# Processamento.net
KiCad netlist of a schematic drawn in Altium Designer
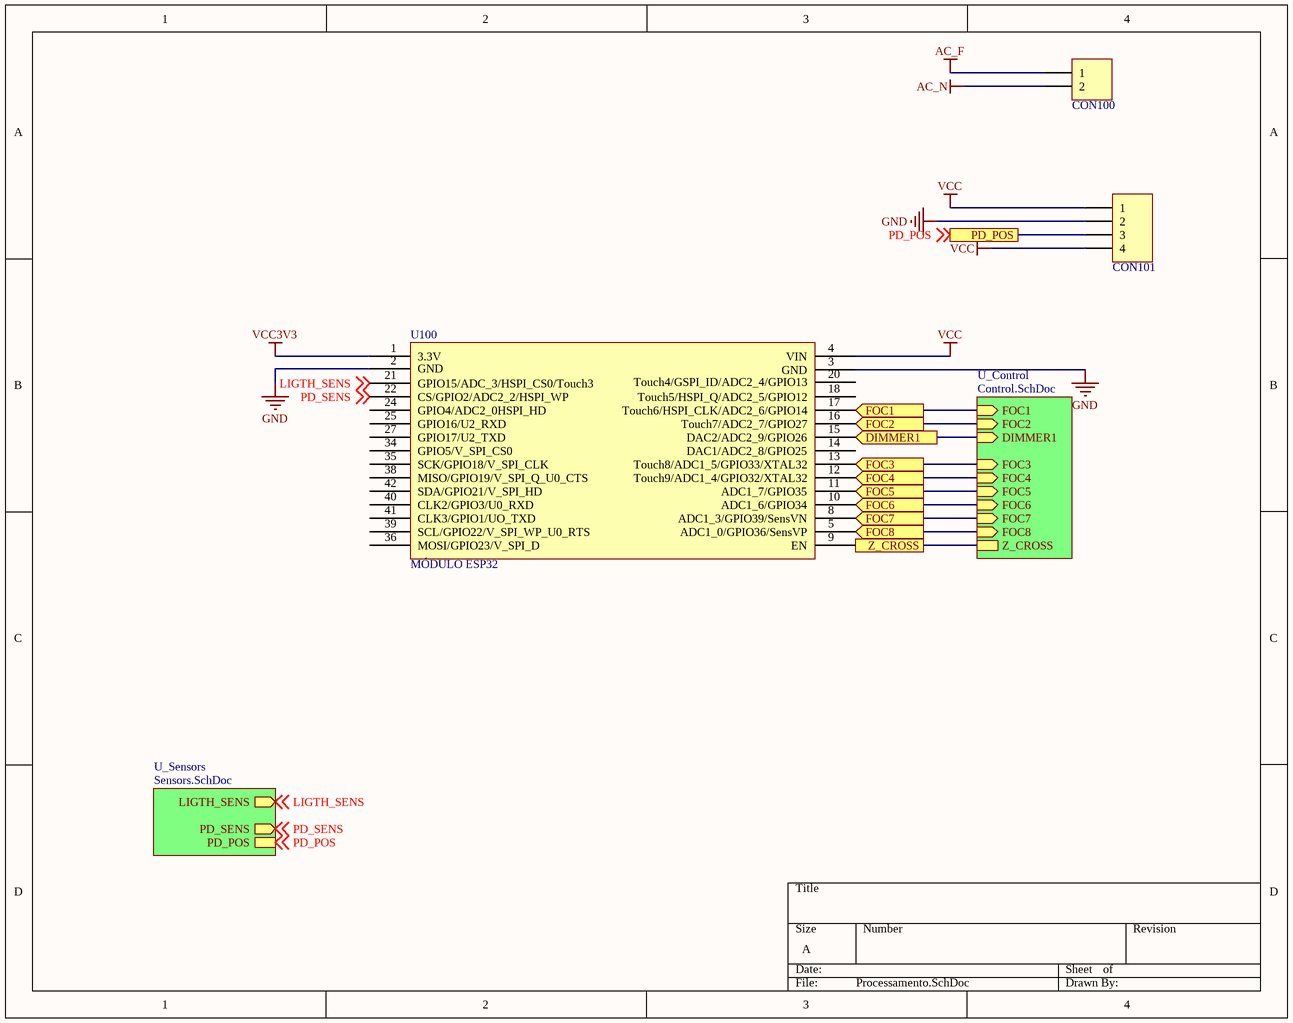
[diagram p0: Processamento.SchDoc]

(export (version "E")
  (design (tool "Eeschema 10.0.6"))
  (components
    (comp (ref "CON100")
      (value "TERM BLOCK 2POS")
      (footprint "STL:MSTBA 2G")
      (description "TERM BLOCK HDR 2POS R/A 5.08MM")
      (fields
        (field (name "MANUFACTURER") "Phoenix Contact")
        (field (name "MANUFACTURER PART NUMBER") "1757242")
      )
      (libsource (lib "STL") (part "TERM BLOCK HEADER 2POS R/A 5.08MM"))
    )
    (comp (ref "CON101")
      (value "TERM BLOCK 4POS")
      (footprint "STL:MSTBA 4G")
      (description "TERM BLOCK HDR 4POS R/A 5.08MM")
      (libsource (lib "STL") (part "TERM BLOCK HEADER 4POS R/A 5.08MM"))
    )
    (comp (ref "U100")
      (value "MÓDULO ESP32")
      (footprint "STL:ESP32 MOD")
      (libsource (lib "STL") (part "IC MICOCONTROLADOR ESP32 MODULO"))
    )
  )
  (nets
    (net (code "1") (name "/DIMMER1") (class "Default")
      (node (ref "U100") (pin "15") (pinfunction "DAC2/ADC2_9/GPIO26_15") (pintype "passive"))
    )
    (net (code "2") (name "/FOC1") (class "Default")
      (node (ref "U100") (pin "17") (pinfunction "Touch6/HSPI_CLK/ADC2_6/GPIO14_17") (pintype "passive"))
    )
    (net (code "3") (name "/FOC2") (class "Default")
      (node (ref "U100") (pin "16") (pinfunction "Touch7/ADC2_7/GPIO27_16") (pintype "passive"))
    )
    (net (code "4") (name "/FOC3") (class "Default")
      (node (ref "U100") (pin "13") (pinfunction "Touch8/ADC1_5/GPIO33/XTAL32_13") (pintype "passive"))
    )
    (net (code "5") (name "/FOC4") (class "Default")
      (node (ref "U100") (pin "12") (pinfunction "Touch9/ADC1_4/GPIO32/XTAL32_12") (pintype "passive"))
    )
    (net (code "6") (name "/FOC5") (class "Default")
      (node (ref "U100") (pin "11") (pinfunction "ADC1_7/GPIO35_11") (pintype "passive"))
    )
    (net (code "7") (name "/FOC6") (class "Default")
      (node (ref "U100") (pin "10") (pinfunction "ADC1_6/GPIO34_10") (pintype "passive"))
    )
    (net (code "8") (name "/FOC7") (class "Default")
      (node (ref "U100") (pin "8") (pinfunction "ADC1_3/GPIO39/SensVN_8") (pintype "passive"))
    )
    (net (code "9") (name "/FOC8") (class "Default")
      (node (ref "U100") (pin "5") (pinfunction "ADC1_0/GPIO36/SensVP_5") (pintype "passive"))
    )
    (net (code "10") (name "/Z_CROSS") (class "Default")
      (node (ref "U100") (pin "9") (pinfunction "EN_9") (pintype "passive"))
    )
    (net (code "11") (name "AC_F") (class "Default")
      (node (ref "CON100") (pin "1") (pinfunction "1_1") (pintype "passive"))
    )
    (net (code "12") (name "AC_N") (class "Default")
      (node (ref "CON100") (pin "2") (pinfunction "2_2") (pintype "passive"))
    )
    (net (code "13") (name "GND") (class "Default")
      (node (ref "CON101") (pin "2") (pinfunction "2_2") (pintype "passive"))
      (node (ref "U100") (pin "2") (pinfunction "GND_2") (pintype "power_in"))
      (node (ref "U100") (pin "3") (pinfunction "GND_3") (pintype "passive"))
    )
    (net (code "14") (name "LIGTH_SENS") (class "Default")
      (node (ref "U100") (pin "21") (pinfunction "GPIO15/ADC_3/HSPI_CS0/Touch3_21") (pintype "passive"))
    )
    (net (code "15") (name "PD_POS") (class "Default")
      (node (ref "CON101") (pin "3") (pinfunction "3_3") (pintype "passive"))
    )
    (net (code "16") (name "PD_SENS") (class "Default")
      (node (ref "U100") (pin "22") (pinfunction "CS/GPIO2/ADC2_2/HSPI_WP_22") (pintype "passive"))
    )
    (net (code "17") (name "VCC") (class "Default")
      (node (ref "CON101") (pin "1") (pinfunction "1_1") (pintype "passive"))
      (node (ref "CON101") (pin "4") (pinfunction "4_4") (pintype "passive"))
      (node (ref "U100") (pin "4") (pinfunction "VIN_4") (pintype "passive"))
    )
    (net (code "18") (name "VCC3V3") (class "Default")
      (node (ref "U100") (pin "1") (pinfunction "3.3V_1") (pintype "power_in"))
    )
    (net (code "19") (name "unconnected-(U100-CLK2{slash}GPIO3{slash}U0_RXD-Pad40)") (class "Default")
      (node (ref "U100") (pin "40") (pinfunction "CLK2/GPIO3/U0_RXD_40") (pintype "passive"))
    )
    (net (code "20") (name "unconnected-(U100-CLK3{slash}GPIO1{slash}UO_TXD-Pad41)") (class "Default")
      (node (ref "U100") (pin "41") (pinfunction "CLK3/GPIO1/UO_TXD_41") (pintype "passive"))
    )
    (net (code "21") (name "unconnected-(U100-DAC1{slash}ADC2_8{slash}GPIO25-Pad14)") (class "Default")
      (node (ref "U100") (pin "14") (pinfunction "DAC1/ADC2_8/GPIO25_14") (pintype "passive"))
    )
    (net (code "22") (name "unconnected-(U100-GPIO4{slash}ADC2_0HSPI_HD-Pad24)") (class "Default")
      (node (ref "U100") (pin "24") (pinfunction "GPIO4/ADC2_0HSPI_HD_24") (pintype "passive"))
    )
    (net (code "23") (name "unconnected-(U100-GPIO5{slash}V_SPI_CS0-Pad34)") (class "Default")
      (node (ref "U100") (pin "34") (pinfunction "GPIO5/V_SPI_CS0_34") (pintype "passive"))
    )
    (net (code "24") (name "unconnected-(U100-GPIO16{slash}U2_RXD-Pad25)") (class "Default")
      (node (ref "U100") (pin "25") (pinfunction "GPIO16/U2_RXD_25") (pintype "passive"))
    )
    (net (code "25") (name "unconnected-(U100-GPIO17{slash}U2_TXD-Pad27)") (class "Default")
      (node (ref "U100") (pin "27") (pinfunction "GPIO17/U2_TXD_27") (pintype "passive"))
    )
    (net (code "26") (name "unconnected-(U100-MISO{slash}GPIO19{slash}V_SPI_Q_U0_CTS-Pad38)") (class "Default")
      (node (ref "U100") (pin "38") (pinfunction "MISO/GPIO19/V_SPI_Q_U0_CTS_38") (pintype "passive"))
    )
    (net (code "27") (name "unconnected-(U100-MOSI{slash}GPIO23{slash}V_SPI_D-Pad36)") (class "Default")
      (node (ref "U100") (pin "36") (pinfunction "MOSI/GPIO23/V_SPI_D_36") (pintype "passive"))
    )
    (net (code "28") (name "unconnected-(U100-SCK{slash}GPIO18{slash}V_SPI_CLK-Pad35)") (class "Default")
      (node (ref "U100") (pin "35") (pinfunction "SCK/GPIO18/V_SPI_CLK_35") (pintype "passive"))
    )
    (net (code "29") (name "unconnected-(U100-SCL{slash}GPIO22{slash}V_SPI_WP_U0_RTS-Pad39)") (class "Default")
      (node (ref "U100") (pin "39") (pinfunction "SCL/GPIO22/V_SPI_WP_U0_RTS_39") (pintype "passive"))
    )
    (net (code "30") (name "unconnected-(U100-SDA{slash}GPIO21{slash}V_SPI_HD-Pad42)") (class "Default")
      (node (ref "U100") (pin "42") (pinfunction "SDA/GPIO21/V_SPI_HD_42") (pintype "passive"))
    )
    (net (code "31") (name "unconnected-(U100-Touch4{slash}GSPI_ID{slash}ADC2_4{slash}GPIO13-Pad20)") (class "Default")
      (node (ref "U100") (pin "20") (pinfunction "Touch4/GSPI_ID/ADC2_4/GPIO13_20") (pintype "passive"))
    )
    (net (code "32") (name "unconnected-(U100-Touch5{slash}HSPI_Q{slash}ADC2_5{slash}GPIO12-Pad18)") (class "Default")
      (node (ref "U100") (pin "18") (pinfunction "Touch5/HSPI_Q/ADC2_5/GPIO12_18") (pintype "passive"))
    )
  )
)
